# BSeriesPlug.net
KiCad netlist of a schematic drawn in EAGLE
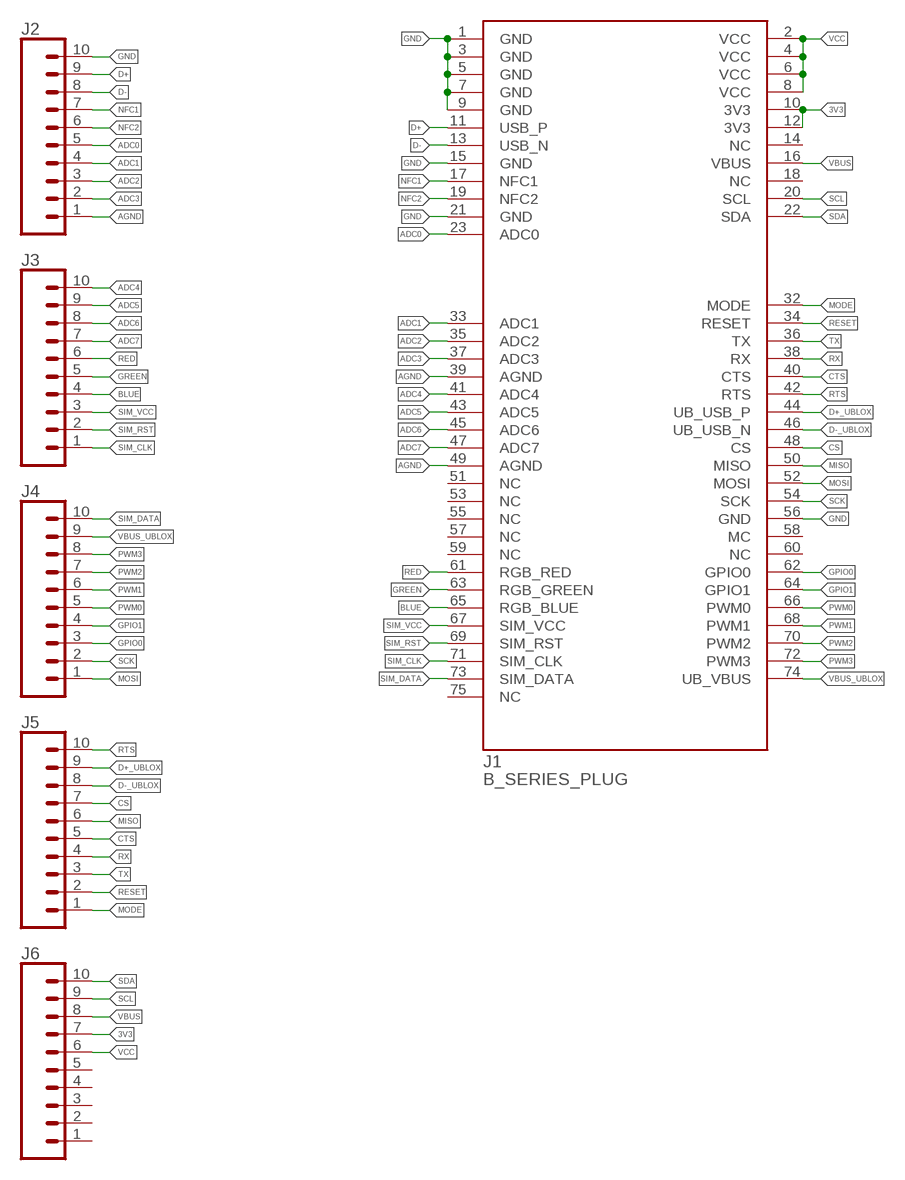
[diagram p0: schematic, sheet 1]

(export (version "E")
  (design (tool "Eeschema 10.0.6"))
  (components
    (comp (ref "J1")
      (value "B_SERIES_PLUG")
      (footprint "eagle-import:M.2-CARD-E-22")
      (libsource (lib "eagle-import") (part "B_SERIES_PLUG"))
    )
    (comp (ref "J2")
      (value "CONN_10\"")
      (footprint "eagle-import:1X10")
      (libsource (lib "eagle-import") (part "CONN_10{dblquote}"))
    )
    (comp (ref "J3")
      (value "CONN_10\"")
      (footprint "eagle-import:1X10")
      (libsource (lib "eagle-import") (part "CONN_10{dblquote}"))
    )
    (comp (ref "J4")
      (value "CONN_10\"")
      (footprint "eagle-import:1X10")
      (libsource (lib "eagle-import") (part "CONN_10{dblquote}"))
    )
    (comp (ref "J5")
      (value "CONN_10\"")
      (footprint "eagle-import:1X10")
      (libsource (lib "eagle-import") (part "CONN_10{dblquote}"))
    )
    (comp (ref "J6")
      (value "CONN_10\"")
      (footprint "eagle-import:1X10")
      (libsource (lib "eagle-import") (part "CONN_10{dblquote}"))
    )
  )
  (nets
    (net (code "1") (name "3V3") (class "Default")
      (node (ref "J1") (pin "10") (pinfunction "3V3_10") (pintype "power_in"))
      (node (ref "J1") (pin "12") (pinfunction "3V3_12") (pintype "power_in"))
      (node (ref "J6") (pin "7") (pinfunction "7_7") (pintype "passive"))
    )
    (net (code "2") (name "ADC0") (class "Default")
      (node (ref "J1") (pin "23") (pinfunction "ADC0_23") (pintype "bidirectional"))
      (node (ref "J2") (pin "5") (pinfunction "5_5") (pintype "passive"))
    )
    (net (code "3") (name "ADC1") (class "Default")
      (node (ref "J1") (pin "33") (pinfunction "ADC1_33") (pintype "bidirectional"))
      (node (ref "J2") (pin "4") (pinfunction "4_4") (pintype "passive"))
    )
    (net (code "4") (name "ADC2") (class "Default")
      (node (ref "J1") (pin "35") (pinfunction "ADC2_35") (pintype "bidirectional"))
      (node (ref "J2") (pin "3") (pinfunction "3_3") (pintype "passive"))
    )
    (net (code "5") (name "ADC3") (class "Default")
      (node (ref "J1") (pin "37") (pinfunction "ADC3_37") (pintype "bidirectional"))
      (node (ref "J2") (pin "2") (pinfunction "2_2") (pintype "passive"))
    )
    (net (code "6") (name "ADC4") (class "Default")
      (node (ref "J1") (pin "41") (pinfunction "ADC4_41") (pintype "bidirectional"))
      (node (ref "J3") (pin "10") (pinfunction "10_10") (pintype "passive"))
    )
    (net (code "7") (name "ADC5") (class "Default")
      (node (ref "J1") (pin "43") (pinfunction "ADC5_43") (pintype "bidirectional"))
      (node (ref "J3") (pin "9") (pinfunction "9_9") (pintype "passive"))
    )
    (net (code "8") (name "ADC6") (class "Default")
      (node (ref "J1") (pin "45") (pinfunction "ADC6_45") (pintype "bidirectional"))
      (node (ref "J3") (pin "8") (pinfunction "8_8") (pintype "passive"))
    )
    (net (code "9") (name "ADC7") (class "Default")
      (node (ref "J1") (pin "47") (pinfunction "ADC7_47") (pintype "bidirectional"))
      (node (ref "J3") (pin "7") (pinfunction "7_7") (pintype "passive"))
    )
    (net (code "10") (name "AGND") (class "Default")
      (node (ref "J1") (pin "39") (pinfunction "AGND_39") (pintype "power_in"))
      (node (ref "J1") (pin "49") (pinfunction "AGND_49") (pintype "power_in"))
      (node (ref "J2") (pin "1") (pinfunction "1_1") (pintype "passive"))
    )
    (net (code "11") (name "BLUE") (class "Default")
      (node (ref "J1") (pin "65") (pinfunction "RGB_BLUE_65") (pintype "bidirectional"))
      (node (ref "J3") (pin "4") (pinfunction "4_4") (pintype "passive"))
    )
    (net (code "12") (name "CS") (class "Default")
      (node (ref "J1") (pin "48") (pinfunction "CS_48") (pintype "bidirectional"))
      (node (ref "J5") (pin "7") (pinfunction "7_7") (pintype "passive"))
    )
    (net (code "13") (name "CTS") (class "Default")
      (node (ref "J1") (pin "40") (pinfunction "CTS_40") (pintype "bidirectional"))
      (node (ref "J5") (pin "5") (pinfunction "5_5") (pintype "passive"))
    )
    (net (code "14") (name "D+") (class "Default")
      (node (ref "J1") (pin "11") (pinfunction "USB_P_11") (pintype "bidirectional"))
      (node (ref "J2") (pin "9") (pinfunction "9_9") (pintype "passive"))
    )
    (net (code "15") (name "D+_UBLOX") (class "Default")
      (node (ref "J1") (pin "44") (pinfunction "UB_USB_P_44") (pintype "bidirectional"))
      (node (ref "J5") (pin "9") (pinfunction "9_9") (pintype "passive"))
    )
    (net (code "16") (name "D-") (class "Default")
      (node (ref "J1") (pin "13") (pinfunction "USB_N_13") (pintype "bidirectional"))
      (node (ref "J2") (pin "8") (pinfunction "8_8") (pintype "passive"))
    )
    (net (code "17") (name "D-_UBLOX") (class "Default")
      (node (ref "J1") (pin "46") (pinfunction "UB_USB_N_46") (pintype "bidirectional"))
      (node (ref "J5") (pin "8") (pinfunction "8_8") (pintype "passive"))
    )
    (net (code "18") (name "GND") (class "Default")
      (node (ref "J1") (pin "1") (pinfunction "GND_1") (pintype "power_in"))
      (node (ref "J1") (pin "15") (pinfunction "GND_15") (pintype "power_in"))
      (node (ref "J1") (pin "21") (pinfunction "GND_21") (pintype "power_in"))
      (node (ref "J1") (pin "3") (pinfunction "GND_3") (pintype "power_in"))
      (node (ref "J1") (pin "5") (pinfunction "GND_5") (pintype "power_in"))
      (node (ref "J1") (pin "56") (pinfunction "GND_56") (pintype "power_in"))
      (node (ref "J1") (pin "7") (pinfunction "GND_7") (pintype "power_in"))
      (node (ref "J1") (pin "9") (pinfunction "GND_9") (pintype "power_in"))
      (node (ref "J2") (pin "10") (pinfunction "10_10") (pintype "passive"))
    )
    (net (code "19") (name "GPIO0") (class "Default")
      (node (ref "J1") (pin "62") (pinfunction "GPIO0_62") (pintype "bidirectional"))
      (node (ref "J4") (pin "3") (pinfunction "3_3") (pintype "passive"))
    )
    (net (code "20") (name "GPIO1") (class "Default")
      (node (ref "J1") (pin "64") (pinfunction "GPIO1_64") (pintype "bidirectional"))
      (node (ref "J4") (pin "4") (pinfunction "4_4") (pintype "passive"))
    )
    (net (code "21") (name "GREEN") (class "Default")
      (node (ref "J1") (pin "63") (pinfunction "RGB_GREEN_63") (pintype "bidirectional"))
      (node (ref "J3") (pin "5") (pinfunction "5_5") (pintype "passive"))
    )
    (net (code "22") (name "MISO") (class "Default")
      (node (ref "J1") (pin "50") (pinfunction "MISO_50") (pintype "bidirectional"))
      (node (ref "J5") (pin "6") (pinfunction "6_6") (pintype "passive"))
    )
    (net (code "23") (name "MODE") (class "Default")
      (node (ref "J1") (pin "32") (pinfunction "MODE_32") (pintype "bidirectional"))
      (node (ref "J5") (pin "1") (pinfunction "1_1") (pintype "passive"))
    )
    (net (code "24") (name "MOSI") (class "Default")
      (node (ref "J1") (pin "52") (pinfunction "MOSI_52") (pintype "bidirectional"))
      (node (ref "J4") (pin "1") (pinfunction "1_1") (pintype "passive"))
    )
    (net (code "25") (name "NFC1") (class "Default")
      (node (ref "J1") (pin "17") (pinfunction "NFC1_17") (pintype "bidirectional"))
      (node (ref "J2") (pin "7") (pinfunction "7_7") (pintype "passive"))
    )
    (net (code "26") (name "NFC2") (class "Default")
      (node (ref "J1") (pin "19") (pinfunction "NFC2_19") (pintype "bidirectional"))
      (node (ref "J2") (pin "6") (pinfunction "6_6") (pintype "passive"))
    )
    (net (code "27") (name "PWM0") (class "Default")
      (node (ref "J1") (pin "66") (pinfunction "PWM0_66") (pintype "bidirectional"))
      (node (ref "J4") (pin "5") (pinfunction "5_5") (pintype "passive"))
    )
    (net (code "28") (name "PWM1") (class "Default")
      (node (ref "J1") (pin "68") (pinfunction "PWM1_68") (pintype "bidirectional"))
      (node (ref "J4") (pin "6") (pinfunction "6_6") (pintype "passive"))
    )
    (net (code "29") (name "PWM2") (class "Default")
      (node (ref "J1") (pin "70") (pinfunction "PWM2_70") (pintype "bidirectional"))
      (node (ref "J4") (pin "7") (pinfunction "7_7") (pintype "passive"))
    )
    (net (code "30") (name "PWM3") (class "Default")
      (node (ref "J1") (pin "72") (pinfunction "PWM3_72") (pintype "bidirectional"))
      (node (ref "J4") (pin "8") (pinfunction "8_8") (pintype "passive"))
    )
    (net (code "31") (name "RED") (class "Default")
      (node (ref "J1") (pin "61") (pinfunction "RGB_RED_61") (pintype "bidirectional"))
      (node (ref "J3") (pin "6") (pinfunction "6_6") (pintype "passive"))
    )
    (net (code "32") (name "RESET") (class "Default")
      (node (ref "J1") (pin "34") (pinfunction "RESET_34") (pintype "bidirectional"))
      (node (ref "J5") (pin "2") (pinfunction "2_2") (pintype "passive"))
    )
    (net (code "33") (name "RTS") (class "Default")
      (node (ref "J1") (pin "42") (pinfunction "RTS_42") (pintype "bidirectional"))
      (node (ref "J5") (pin "10") (pinfunction "10_10") (pintype "passive"))
    )
    (net (code "34") (name "RX") (class "Default")
      (node (ref "J1") (pin "38") (pinfunction "RX_38") (pintype "bidirectional"))
      (node (ref "J5") (pin "4") (pinfunction "4_4") (pintype "passive"))
    )
    (net (code "35") (name "SCK") (class "Default")
      (node (ref "J1") (pin "54") (pinfunction "SCK_54") (pintype "bidirectional"))
      (node (ref "J4") (pin "2") (pinfunction "2_2") (pintype "passive"))
    )
    (net (code "36") (name "SCL") (class "Default")
      (node (ref "J1") (pin "20") (pinfunction "SCL_20") (pintype "bidirectional"))
      (node (ref "J6") (pin "9") (pinfunction "9_9") (pintype "passive"))
    )
    (net (code "37") (name "SDA") (class "Default")
      (node (ref "J1") (pin "22") (pinfunction "SDA_22") (pintype "bidirectional"))
      (node (ref "J6") (pin "10") (pinfunction "10_10") (pintype "passive"))
    )
    (net (code "38") (name "SIM_CLK") (class "Default")
      (node (ref "J1") (pin "71") (pinfunction "SIM_CLK_71") (pintype "bidirectional"))
      (node (ref "J3") (pin "1") (pinfunction "1_1") (pintype "passive"))
    )
    (net (code "39") (name "SIM_DATA") (class "Default")
      (node (ref "J1") (pin "73") (pinfunction "SIM_DATA_73") (pintype "bidirectional"))
      (node (ref "J4") (pin "10") (pinfunction "10_10") (pintype "passive"))
    )
    (net (code "40") (name "SIM_RST") (class "Default")
      (node (ref "J1") (pin "69") (pinfunction "SIM_RST_69") (pintype "bidirectional"))
      (node (ref "J3") (pin "2") (pinfunction "2_2") (pintype "passive"))
    )
    (net (code "41") (name "SIM_VCC") (class "Default")
      (node (ref "J1") (pin "67") (pinfunction "SIM_VCC_67") (pintype "power_in"))
      (node (ref "J3") (pin "3") (pinfunction "3_3") (pintype "passive"))
    )
    (net (code "42") (name "TX") (class "Default")
      (node (ref "J1") (pin "36") (pinfunction "TX_36") (pintype "bidirectional"))
      (node (ref "J5") (pin "3") (pinfunction "3_3") (pintype "passive"))
    )
    (net (code "43") (name "VBUS") (class "Default")
      (node (ref "J1") (pin "16") (pinfunction "VBUS_16") (pintype "power_in"))
      (node (ref "J6") (pin "8") (pinfunction "8_8") (pintype "passive"))
    )
    (net (code "44") (name "VBUS_UBLOX") (class "Default")
      (node (ref "J1") (pin "74") (pinfunction "UB_VBUS_74") (pintype "power_in"))
      (node (ref "J4") (pin "9") (pinfunction "9_9") (pintype "passive"))
    )
    (net (code "45") (name "VCC") (class "Default")
      (node (ref "J1") (pin "2") (pinfunction "VCC_2") (pintype "power_in"))
      (node (ref "J1") (pin "4") (pinfunction "VCC_4") (pintype "power_in"))
      (node (ref "J1") (pin "6") (pinfunction "VCC_6") (pintype "power_in"))
      (node (ref "J1") (pin "8") (pinfunction "VCC_8") (pintype "power_in"))
      (node (ref "J6") (pin "6") (pinfunction "6_6") (pintype "passive"))
    )
    (net (code "46") (name "unconnected-(J1-MC-Pad58)") (class "Default")
      (node (ref "J1") (pin "58") (pinfunction "MC_58") (pintype "bidirectional"))
    )
    (net (code "47") (name "unconnected-(J1-NC-Pad14)") (class "Default")
      (node (ref "J1") (pin "14") (pinfunction "NC_14") (pintype "bidirectional"))
    )
    (net (code "48") (name "unconnected-(J1-NC-Pad18)") (class "Default")
      (node (ref "J1") (pin "18") (pinfunction "NC_18") (pintype "bidirectional"))
    )
    (net (code "49") (name "unconnected-(J1-NC-Pad51)") (class "Default")
      (node (ref "J1") (pin "51") (pinfunction "NC_51") (pintype "bidirectional"))
    )
    (net (code "50") (name "unconnected-(J1-NC-Pad53)") (class "Default")
      (node (ref "J1") (pin "53") (pinfunction "NC_53") (pintype "bidirectional"))
    )
    (net (code "51") (name "unconnected-(J1-NC-Pad55)") (class "Default")
      (node (ref "J1") (pin "55") (pinfunction "NC_55") (pintype "bidirectional"))
    )
    (net (code "52") (name "unconnected-(J1-NC-Pad57)") (class "Default")
      (node (ref "J1") (pin "57") (pinfunction "NC_57") (pintype "bidirectional"))
    )
    (net (code "53") (name "unconnected-(J1-NC-Pad59)") (class "Default")
      (node (ref "J1") (pin "59") (pinfunction "NC_59") (pintype "bidirectional"))
    )
    (net (code "54") (name "unconnected-(J1-NC-Pad60)") (class "Default")
      (node (ref "J1") (pin "60") (pinfunction "NC_60") (pintype "bidirectional"))
    )
    (net (code "55") (name "unconnected-(J1-NC-Pad75)") (class "Default")
      (node (ref "J1") (pin "75") (pinfunction "NC_75") (pintype "bidirectional"))
    )
    (net (code "56") (name "unconnected-(J6-Pad1)") (class "Default")
      (node (ref "J6") (pin "1") (pinfunction "1_1") (pintype "passive"))
    )
    (net (code "57") (name "unconnected-(J6-Pad2)") (class "Default")
      (node (ref "J6") (pin "2") (pinfunction "2_2") (pintype "passive"))
    )
    (net (code "58") (name "unconnected-(J6-Pad3)") (class "Default")
      (node (ref "J6") (pin "3") (pinfunction "3_3") (pintype "passive"))
    )
    (net (code "59") (name "unconnected-(J6-Pad4)") (class "Default")
      (node (ref "J6") (pin "4") (pinfunction "4_4") (pintype "passive"))
    )
    (net (code "60") (name "unconnected-(J6-Pad5)") (class "Default")
      (node (ref "J6") (pin "5") (pinfunction "5_5") (pintype "passive"))
    )
  )
)
